# ArdIOShieldV02.net
KiCad netlist of a schematic drawn in EAGLE
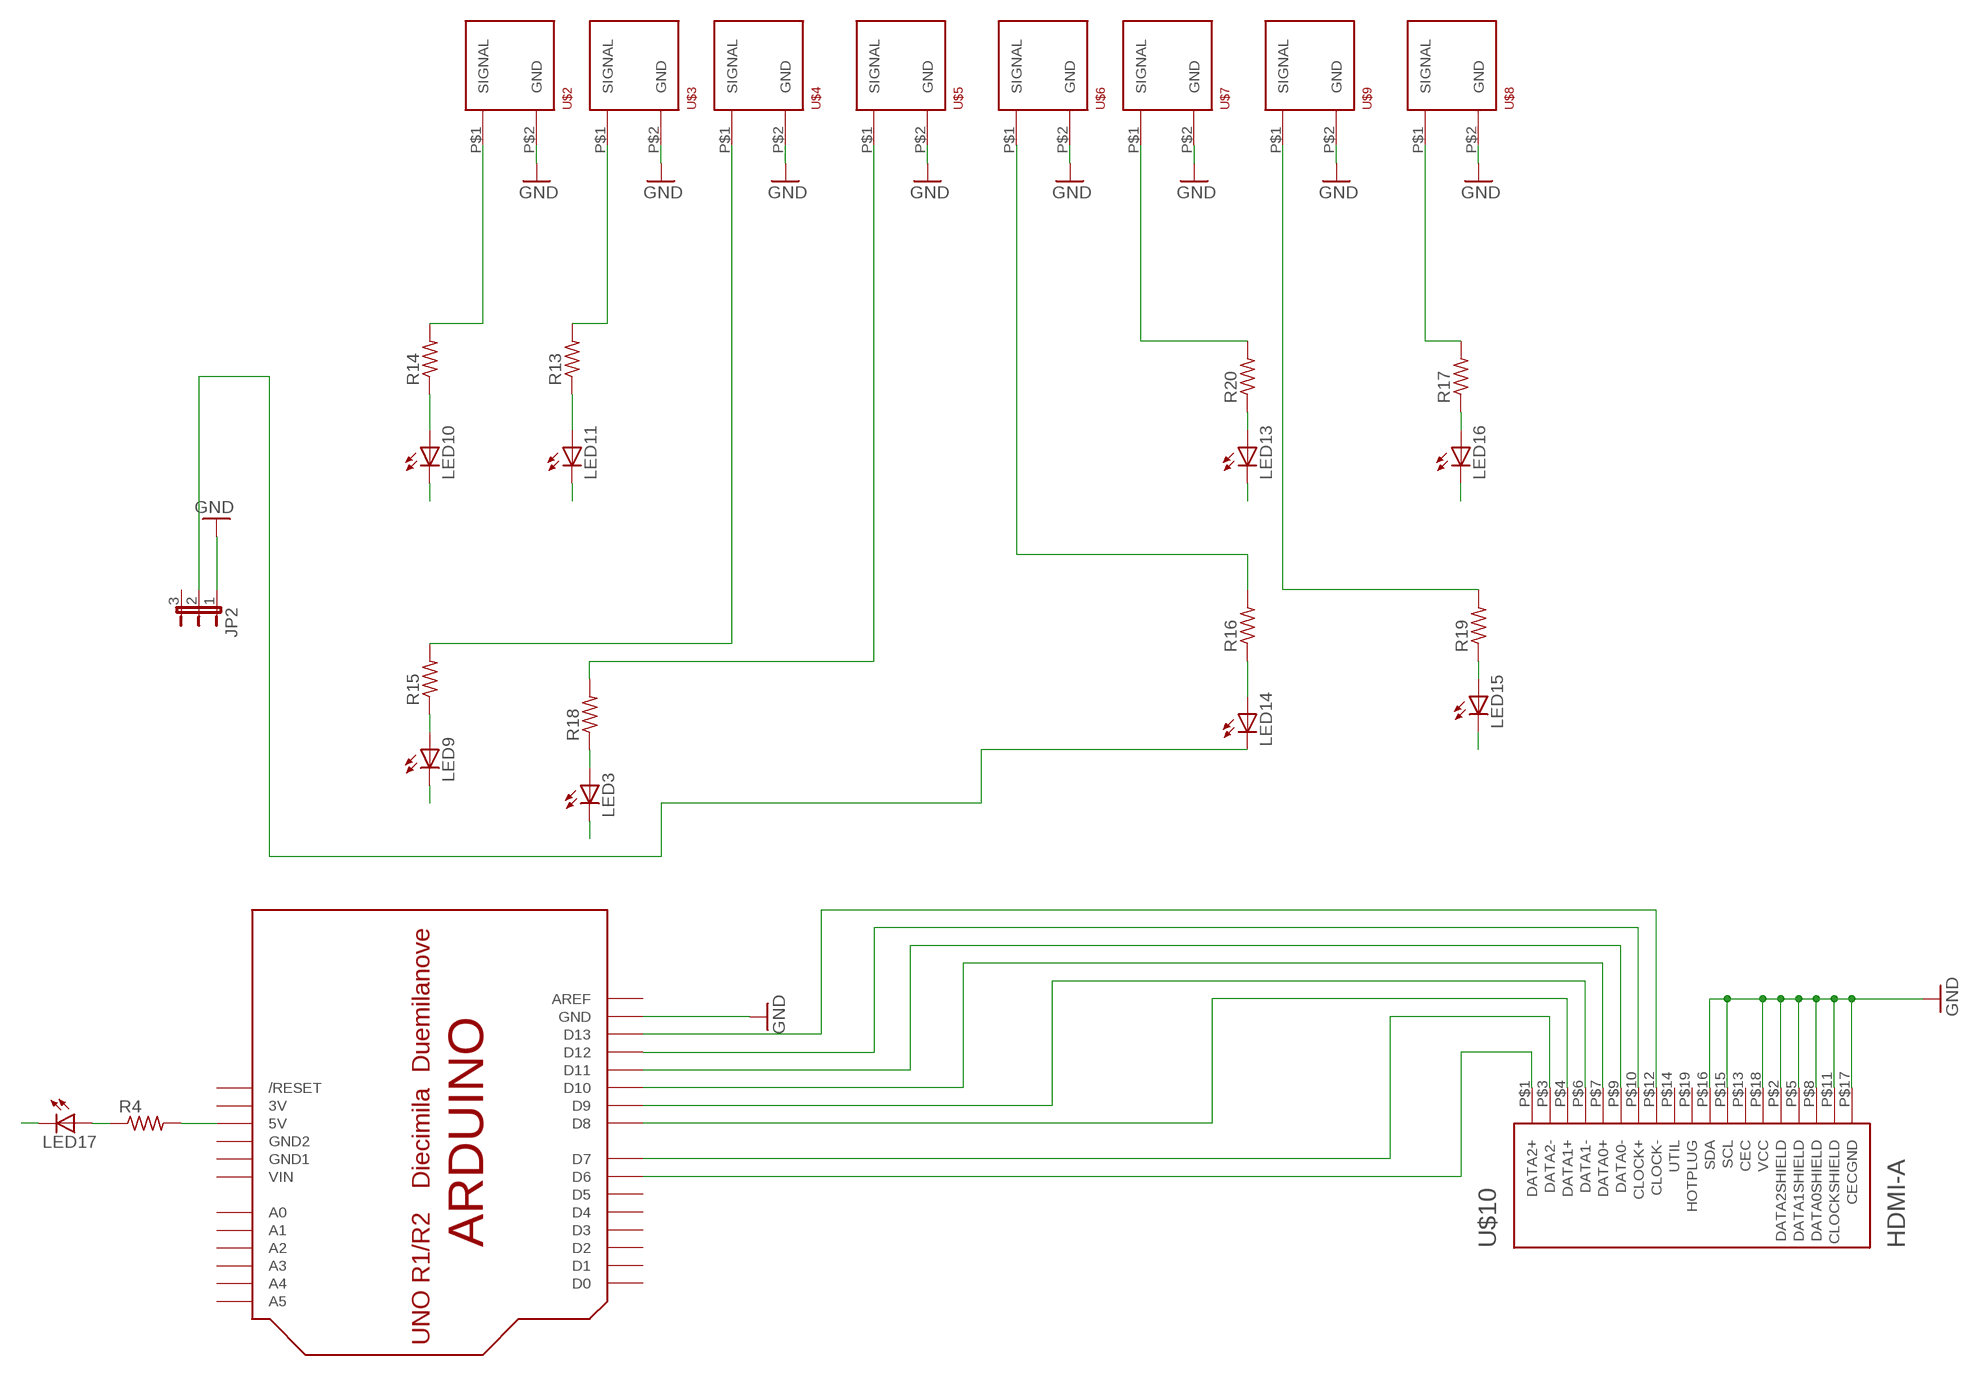
[diagram p0: schematic, sheet 1]

(export (version "E")
  (design (tool "Eeschema 10.0.6"))
  (components
    (comp (ref "JP2")
      (value "JP2E")
      (footprint "eagle-import:JP2")
      (libsource (lib "eagle-import") (part "JP2E"))
    )
    (comp (ref "LED3")
      (value "LEDCHIP-LED0805")
      (footprint "eagle-import:CHIP-LED0805")
      (libsource (lib "eagle-import") (part "LEDCHIP-LED0805"))
    )
    (comp (ref "LED9")
      (value "LEDCHIP-LED0805")
      (footprint "eagle-import:CHIP-LED0805")
      (libsource (lib "eagle-import") (part "LEDCHIP-LED0805"))
    )
    (comp (ref "LED10")
      (value "LEDCHIP-LED0805")
      (footprint "eagle-import:CHIP-LED0805")
      (libsource (lib "eagle-import") (part "LEDCHIP-LED0805"))
    )
    (comp (ref "LED11")
      (value "LEDCHIP-LED0805")
      (footprint "eagle-import:CHIP-LED0805")
      (libsource (lib "eagle-import") (part "LEDCHIP-LED0805"))
    )
    (comp (ref "LED13")
      (value "LEDCHIP-LED0805")
      (footprint "eagle-import:CHIP-LED0805")
      (libsource (lib "eagle-import") (part "LEDCHIP-LED0805"))
    )
    (comp (ref "LED14")
      (value "LEDCHIP-LED0805")
      (footprint "eagle-import:CHIP-LED0805")
      (libsource (lib "eagle-import") (part "LEDCHIP-LED0805"))
    )
    (comp (ref "LED15")
      (value "LEDCHIP-LED0805")
      (footprint "eagle-import:CHIP-LED0805")
      (libsource (lib "eagle-import") (part "LEDCHIP-LED0805"))
    )
    (comp (ref "LED16")
      (value "LEDCHIP-LED0805")
      (footprint "eagle-import:CHIP-LED0805")
      (libsource (lib "eagle-import") (part "LEDCHIP-LED0805"))
    )
    (comp (ref "LED17")
      (value "LEDCHIP-LED0805")
      (footprint "eagle-import:CHIP-LED0805")
      (libsource (lib "eagle-import") (part "LEDCHIP-LED0805"))
    )
    (comp (ref "R4")
      (value "R_0603")
      (footprint "eagle-import:0603")
      (libsource (lib "eagle-import") (part "R_0603"))
    )
    (comp (ref "R13")
      (value "R_0603")
      (footprint "eagle-import:0603")
      (libsource (lib "eagle-import") (part "R_0603"))
    )
    (comp (ref "R14")
      (value "R_0603")
      (footprint "eagle-import:0603")
      (libsource (lib "eagle-import") (part "R_0603"))
    )
    (comp (ref "R15")
      (value "R_0603")
      (footprint "eagle-import:0603")
      (libsource (lib "eagle-import") (part "R_0603"))
    )
    (comp (ref "R16")
      (value "R_0603")
      (footprint "eagle-import:0603")
      (libsource (lib "eagle-import") (part "R_0603"))
    )
    (comp (ref "R17")
      (value "R_0603")
      (footprint "eagle-import:0603")
      (libsource (lib "eagle-import") (part "R_0603"))
    )
    (comp (ref "R18")
      (value "R_0603")
      (footprint "eagle-import:0603")
      (libsource (lib "eagle-import") (part "R_0603"))
    )
    (comp (ref "R19")
      (value "R_0603")
      (footprint "eagle-import:0603")
      (libsource (lib "eagle-import") (part "R_0603"))
    )
    (comp (ref "R20")
      (value "R_0603")
      (footprint "eagle-import:0603")
      (libsource (lib "eagle-import") (part "R_0603"))
    )
    (comp (ref "U$1")
      (value "ARDUINO-NOHOLE")
      (footprint "eagle-import:ARDUINO-NOHOLE")
      (libsource (lib "eagle-import") (part "ARDUINO-NOHOLE"))
    )
    (comp (ref "U$2")
      (value "BNC_VERTICAL")
      (footprint "eagle-import:BNC_VERTICAL")
      (libsource (lib "eagle-import") (part "BNC_VERTICAL"))
    )
    (comp (ref "U$3")
      (value "BNC_VERTICAL")
      (footprint "eagle-import:BNC_VERTICAL")
      (libsource (lib "eagle-import") (part "BNC_VERTICAL"))
    )
    (comp (ref "U$4")
      (value "BNC_VERTICAL")
      (footprint "eagle-import:BNC_VERTICAL")
      (libsource (lib "eagle-import") (part "BNC_VERTICAL"))
    )
    (comp (ref "U$5")
      (value "BNC_VERTICAL")
      (footprint "eagle-import:BNC_VERTICAL")
      (libsource (lib "eagle-import") (part "BNC_VERTICAL"))
    )
    (comp (ref "U$6")
      (value "BNC_VERTICAL")
      (footprint "eagle-import:BNC_VERTICAL")
      (libsource (lib "eagle-import") (part "BNC_VERTICAL"))
    )
    (comp (ref "U$7")
      (value "BNC_VERTICAL")
      (footprint "eagle-import:BNC_VERTICAL")
      (libsource (lib "eagle-import") (part "BNC_VERTICAL"))
    )
    (comp (ref "U$8")
      (value "BNC_VERTICAL")
      (footprint "eagle-import:BNC_VERTICAL")
      (libsource (lib "eagle-import") (part "BNC_VERTICAL"))
    )
    (comp (ref "U$9")
      (value "BNC_VERTICAL")
      (footprint "eagle-import:BNC_VERTICAL")
      (libsource (lib "eagle-import") (part "BNC_VERTICAL"))
    )
    (comp (ref "U$10")
      (value "HDMI-A")
      (footprint "eagle-import:HDMI_A")
      (libsource (lib "eagle-import") (part "HDMI-A"))
    )
  )
  (nets
    (net (code "1") (name "/3V") (class "Default")
      (node (ref "U$1") (pin "3V") (pinfunction "3V_3V") (pintype "power_in"))
    )
    (net (code "2") (name "/D6") (class "Default")
      (node (ref "R17") (pin "2") (pinfunction "2_2") (pintype "passive"))
      (node (ref "U$1") (pin "D6") (pinfunction "D6_D6") (pintype "bidirectional"))
      (node (ref "U$10") (pin "P$1") (pinfunction "DATA2+_P$1") (pintype "bidirectional"))
      (node (ref "U$8") (pin "P$1") (pinfunction "SIGNAL_P$1") (pintype "bidirectional"))
    )
    (net (code "3") (name "/D7") (class "Default")
      (node (ref "R19") (pin "2") (pinfunction "2_2") (pintype "passive"))
      (node (ref "U$1") (pin "D7") (pinfunction "D7_D7") (pintype "bidirectional"))
      (node (ref "U$10") (pin "P$3") (pinfunction "DATA2-_P$3") (pintype "bidirectional"))
      (node (ref "U$9") (pin "P$1") (pinfunction "SIGNAL_P$1") (pintype "bidirectional"))
    )
    (net (code "4") (name "/D8") (class "Default")
      (node (ref "R20") (pin "2") (pinfunction "2_2") (pintype "passive"))
      (node (ref "U$1") (pin "D8") (pinfunction "D8_D8") (pintype "bidirectional"))
      (node (ref "U$10") (pin "P$4") (pinfunction "DATA1+_P$4") (pintype "bidirectional"))
      (node (ref "U$7") (pin "P$1") (pinfunction "SIGNAL_P$1") (pintype "bidirectional"))
    )
    (net (code "5") (name "/D9") (class "Default")
      (node (ref "R16") (pin "2") (pinfunction "2_2") (pintype "passive"))
      (node (ref "U$1") (pin "D9") (pinfunction "D9_D9") (pintype "bidirectional"))
      (node (ref "U$10") (pin "P$6") (pinfunction "DATA1-_P$6") (pintype "bidirectional"))
      (node (ref "U$6") (pin "P$1") (pinfunction "SIGNAL_P$1") (pintype "bidirectional"))
    )
    (net (code "6") (name "/D10") (class "Default")
      (node (ref "R18") (pin "2") (pinfunction "2_2") (pintype "passive"))
      (node (ref "U$1") (pin "D10") (pinfunction "D10_D10") (pintype "bidirectional"))
      (node (ref "U$10") (pin "P$7") (pinfunction "DATA0+_P$7") (pintype "bidirectional"))
      (node (ref "U$5") (pin "P$1") (pinfunction "SIGNAL_P$1") (pintype "bidirectional"))
    )
    (net (code "7") (name "/D11") (class "Default")
      (node (ref "R15") (pin "2") (pinfunction "2_2") (pintype "passive"))
      (node (ref "U$1") (pin "D11") (pinfunction "D11_D11") (pintype "bidirectional"))
      (node (ref "U$10") (pin "P$9") (pinfunction "DATA0-_P$9") (pintype "bidirectional"))
      (node (ref "U$4") (pin "P$1") (pinfunction "SIGNAL_P$1") (pintype "bidirectional"))
    )
    (net (code "8") (name "/D12") (class "Default")
      (node (ref "R13") (pin "2") (pinfunction "2_2") (pintype "passive"))
      (node (ref "U$1") (pin "D12") (pinfunction "D12_D12") (pintype "bidirectional"))
      (node (ref "U$10") (pin "P$10") (pinfunction "CLOCK+_P$10") (pintype "bidirectional"))
      (node (ref "U$3") (pin "P$1") (pinfunction "SIGNAL_P$1") (pintype "bidirectional"))
    )
    (net (code "9") (name "/D13") (class "Default")
      (node (ref "R14") (pin "2") (pinfunction "2_2") (pintype "passive"))
      (node (ref "U$1") (pin "D13") (pinfunction "D13_D13") (pintype "bidirectional"))
      (node (ref "U$10") (pin "P$12") (pinfunction "CLOCK-_P$12") (pintype "bidirectional"))
      (node (ref "U$2") (pin "P$1") (pinfunction "SIGNAL_P$1") (pintype "bidirectional"))
    )
    (net (code "10") (name "/GND1") (class "Default")
      (node (ref "U$1") (pin "GND1") (pinfunction "GND1_GND1") (pintype "power_in"))
    )
    (net (code "11") (name "/GND2") (class "Default")
      (node (ref "U$1") (pin "GND2") (pinfunction "GND2_GND2") (pintype "power_in"))
    )
    (net (code "12") (name "/LED") (class "Default")
      (node (ref "JP2") (pin "2") (pinfunction "2_2") (pintype "passive"))
      (node (ref "LED10") (pin "C") (pinfunction "C_C") (pintype "passive"))
      (node (ref "LED11") (pin "C") (pinfunction "C_C") (pintype "passive"))
      (node (ref "LED13") (pin "C") (pinfunction "C_C") (pintype "passive"))
      (node (ref "LED14") (pin "C") (pinfunction "C_C") (pintype "passive"))
      (node (ref "LED15") (pin "C") (pinfunction "C_C") (pintype "passive"))
      (node (ref "LED16") (pin "C") (pinfunction "C_C") (pintype "passive"))
      (node (ref "LED17") (pin "C") (pinfunction "C_C") (pintype "passive"))
      (node (ref "LED3") (pin "C") (pinfunction "C_C") (pintype "passive"))
      (node (ref "LED9") (pin "C") (pinfunction "C_C") (pintype "passive"))
    )
    (net (code "13") (name "/VIN") (class "Default")
      (node (ref "U$1") (pin "VIN") (pinfunction "VIN_VIN") (pintype "power_in"))
    )
    (net (code "14") (name "GND") (class "Default")
      (node (ref "JP2") (pin "1") (pinfunction "1_1") (pintype "passive"))
      (node (ref "U$1") (pin "GND") (pinfunction "GND_GND") (pintype "power_in"))
      (node (ref "U$10") (pin "P$11") (pinfunction "CLOCKSHIELD_P$11") (pintype "bidirectional"))
      (node (ref "U$10") (pin "P$15") (pinfunction "SCL_P$15") (pintype "bidirectional"))
      (node (ref "U$10") (pin "P$16") (pinfunction "SDA_P$16") (pintype "bidirectional"))
      (node (ref "U$10") (pin "P$17") (pinfunction "CECGND_P$17") (pintype "bidirectional"))
      (node (ref "U$10") (pin "P$18") (pinfunction "VCC_P$18") (pintype "bidirectional"))
      (node (ref "U$10") (pin "P$2") (pinfunction "DATA2SHIELD_P$2") (pintype "bidirectional"))
      (node (ref "U$10") (pin "P$5") (pinfunction "DATA1SHIELD_P$5") (pintype "bidirectional"))
      (node (ref "U$10") (pin "P$8") (pinfunction "DATA0SHIELD_P$8") (pintype "bidirectional"))
      (node (ref "U$2") (pin "P$2") (pinfunction "GND_P$2") (pintype "bidirectional"))
      (node (ref "U$3") (pin "P$2") (pinfunction "GND_P$2") (pintype "bidirectional"))
      (node (ref "U$4") (pin "P$2") (pinfunction "GND_P$2") (pintype "bidirectional"))
      (node (ref "U$5") (pin "P$2") (pinfunction "GND_P$2") (pintype "bidirectional"))
      (node (ref "U$6") (pin "P$2") (pinfunction "GND_P$2") (pintype "bidirectional"))
      (node (ref "U$7") (pin "P$2") (pinfunction "GND_P$2") (pintype "bidirectional"))
      (node (ref "U$8") (pin "P$2") (pinfunction "GND_P$2") (pintype "bidirectional"))
      (node (ref "U$9") (pin "P$2") (pinfunction "GND_P$2") (pintype "bidirectional"))
    )
    (net (code "15") (name "Net-(LED3-PadA)") (class "Default")
      (node (ref "LED3") (pin "A") (pinfunction "A_A") (pintype "passive"))
      (node (ref "R18") (pin "1") (pinfunction "1_1") (pintype "passive"))
    )
    (net (code "16") (name "Net-(LED9-PadA)") (class "Default")
      (node (ref "LED9") (pin "A") (pinfunction "A_A") (pintype "passive"))
      (node (ref "R15") (pin "1") (pinfunction "1_1") (pintype "passive"))
    )
    (net (code "17") (name "Net-(LED10-PadA)") (class "Default")
      (node (ref "LED10") (pin "A") (pinfunction "A_A") (pintype "passive"))
      (node (ref "R14") (pin "1") (pinfunction "1_1") (pintype "passive"))
    )
    (net (code "18") (name "Net-(LED11-PadA)") (class "Default")
      (node (ref "LED11") (pin "A") (pinfunction "A_A") (pintype "passive"))
      (node (ref "R13") (pin "1") (pinfunction "1_1") (pintype "passive"))
    )
    (net (code "19") (name "Net-(LED13-PadA)") (class "Default")
      (node (ref "LED13") (pin "A") (pinfunction "A_A") (pintype "passive"))
      (node (ref "R20") (pin "1") (pinfunction "1_1") (pintype "passive"))
    )
    (net (code "20") (name "Net-(LED14-PadA)") (class "Default")
      (node (ref "LED14") (pin "A") (pinfunction "A_A") (pintype "passive"))
      (node (ref "R16") (pin "1") (pinfunction "1_1") (pintype "passive"))
    )
    (net (code "21") (name "Net-(LED15-PadA)") (class "Default")
      (node (ref "LED15") (pin "A") (pinfunction "A_A") (pintype "passive"))
      (node (ref "R19") (pin "1") (pinfunction "1_1") (pintype "passive"))
    )
    (net (code "22") (name "Net-(LED16-PadA)") (class "Default")
      (node (ref "LED16") (pin "A") (pinfunction "A_A") (pintype "passive"))
      (node (ref "R17") (pin "1") (pinfunction "1_1") (pintype "passive"))
    )
    (net (code "23") (name "Net-(LED17-PadA)") (class "Default")
      (node (ref "LED17") (pin "A") (pinfunction "A_A") (pintype "passive"))
      (node (ref "R4") (pin "1") (pinfunction "1_1") (pintype "passive"))
    )
    (net (code "24") (name "Net-(R4-Pad2)") (class "Default")
      (node (ref "R4") (pin "2") (pinfunction "2_2") (pintype "passive"))
      (node (ref "U$1") (pin "5V") (pinfunction "5V_5V") (pintype "power_in"))
    )
    (net (code "25") (name "unconnected-(JP2-Pad3)") (class "Default")
      (node (ref "JP2") (pin "3") (pinfunction "3_3") (pintype "passive"))
    )
    (net (code "26") (name "unconnected-(U$1-PadA0)") (class "Default")
      (node (ref "U$1") (pin "A0") (pinfunction "A0_A0") (pintype "bidirectional"))
    )
    (net (code "27") (name "unconnected-(U$1-PadA1)") (class "Default")
      (node (ref "U$1") (pin "A1") (pinfunction "A1_A1") (pintype "bidirectional"))
    )
    (net (code "28") (name "unconnected-(U$1-PadA2)") (class "Default")
      (node (ref "U$1") (pin "A2") (pinfunction "A2_A2") (pintype "bidirectional"))
    )
    (net (code "29") (name "unconnected-(U$1-PadA3)") (class "Default")
      (node (ref "U$1") (pin "A3") (pinfunction "A3_A3") (pintype "bidirectional"))
    )
    (net (code "30") (name "unconnected-(U$1-PadA4)") (class "Default")
      (node (ref "U$1") (pin "A4") (pinfunction "A4_A4") (pintype "bidirectional"))
    )
    (net (code "31") (name "unconnected-(U$1-PadA5)") (class "Default")
      (node (ref "U$1") (pin "A5") (pinfunction "A5_A5") (pintype "bidirectional"))
    )
    (net (code "32") (name "unconnected-(U$1-PadAREF)") (class "Default")
      (node (ref "U$1") (pin "AREF") (pinfunction "AREF_AREF") (pintype "bidirectional"))
    )
    (net (code "33") (name "unconnected-(U$1-PadD0)") (class "Default")
      (node (ref "U$1") (pin "D0") (pinfunction "D0_D0") (pintype "bidirectional"))
    )
    (net (code "34") (name "unconnected-(U$1-PadD1)") (class "Default")
      (node (ref "U$1") (pin "D1") (pinfunction "D1_D1") (pintype "bidirectional"))
    )
    (net (code "35") (name "unconnected-(U$1-PadD2)") (class "Default")
      (node (ref "U$1") (pin "D2") (pinfunction "D2_D2") (pintype "bidirectional"))
    )
    (net (code "36") (name "unconnected-(U$1-PadD3)") (class "Default")
      (node (ref "U$1") (pin "D3") (pinfunction "D3_D3") (pintype "bidirectional"))
    )
    (net (code "37") (name "unconnected-(U$1-PadD4)") (class "Default")
      (node (ref "U$1") (pin "D4") (pinfunction "D4_D4") (pintype "bidirectional"))
    )
    (net (code "38") (name "unconnected-(U$1-PadD5)") (class "Default")
      (node (ref "U$1") (pin "D5") (pinfunction "D5_D5") (pintype "bidirectional"))
    )
    (net (code "39") (name "unconnected-(U$1-{slash}RESET-PadRESET)") (class "Default")
      (node (ref "U$1") (pin "RESET") (pinfunction "/RESET_RESET") (pintype "bidirectional"))
    )
    (net (code "40") (name "unconnected-(U$10-CEC-PadP$13)") (class "Default")
      (node (ref "U$10") (pin "P$13") (pinfunction "CEC_P$13") (pintype "bidirectional"))
    )
    (net (code "41") (name "unconnected-(U$10-HOTPLUG-PadP$19)") (class "Default")
      (node (ref "U$10") (pin "P$19") (pinfunction "HOTPLUG_P$19") (pintype "bidirectional"))
    )
    (net (code "42") (name "unconnected-(U$10-UTIL-PadP$14)") (class "Default")
      (node (ref "U$10") (pin "P$14") (pinfunction "UTIL_P$14") (pintype "bidirectional"))
    )
  )
)
